# carcomputer_split1_bottom.net
KiCad netlist of a schematic drawn in EAGLE
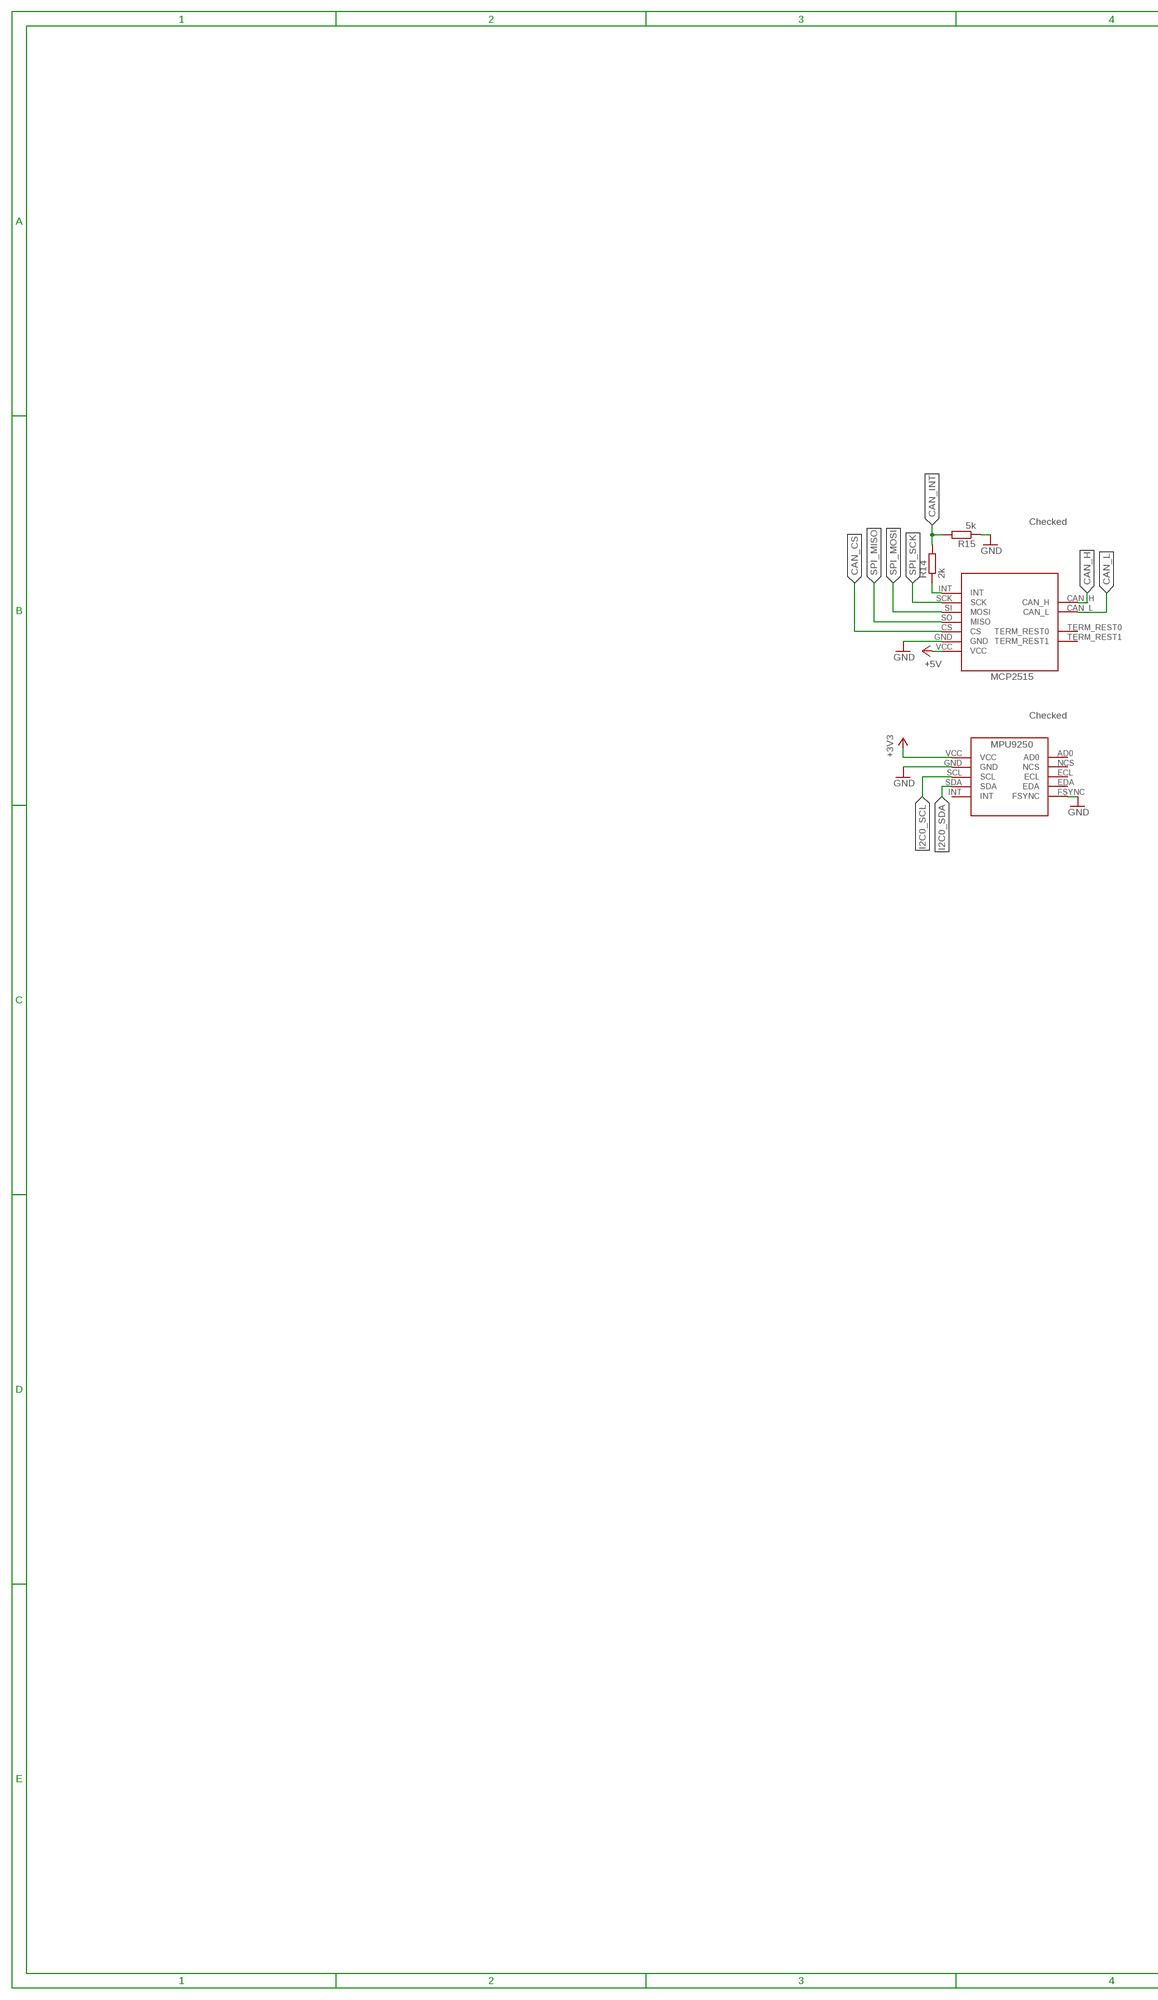
[diagram p0: schematic, sheet 1, part 1 of 2]
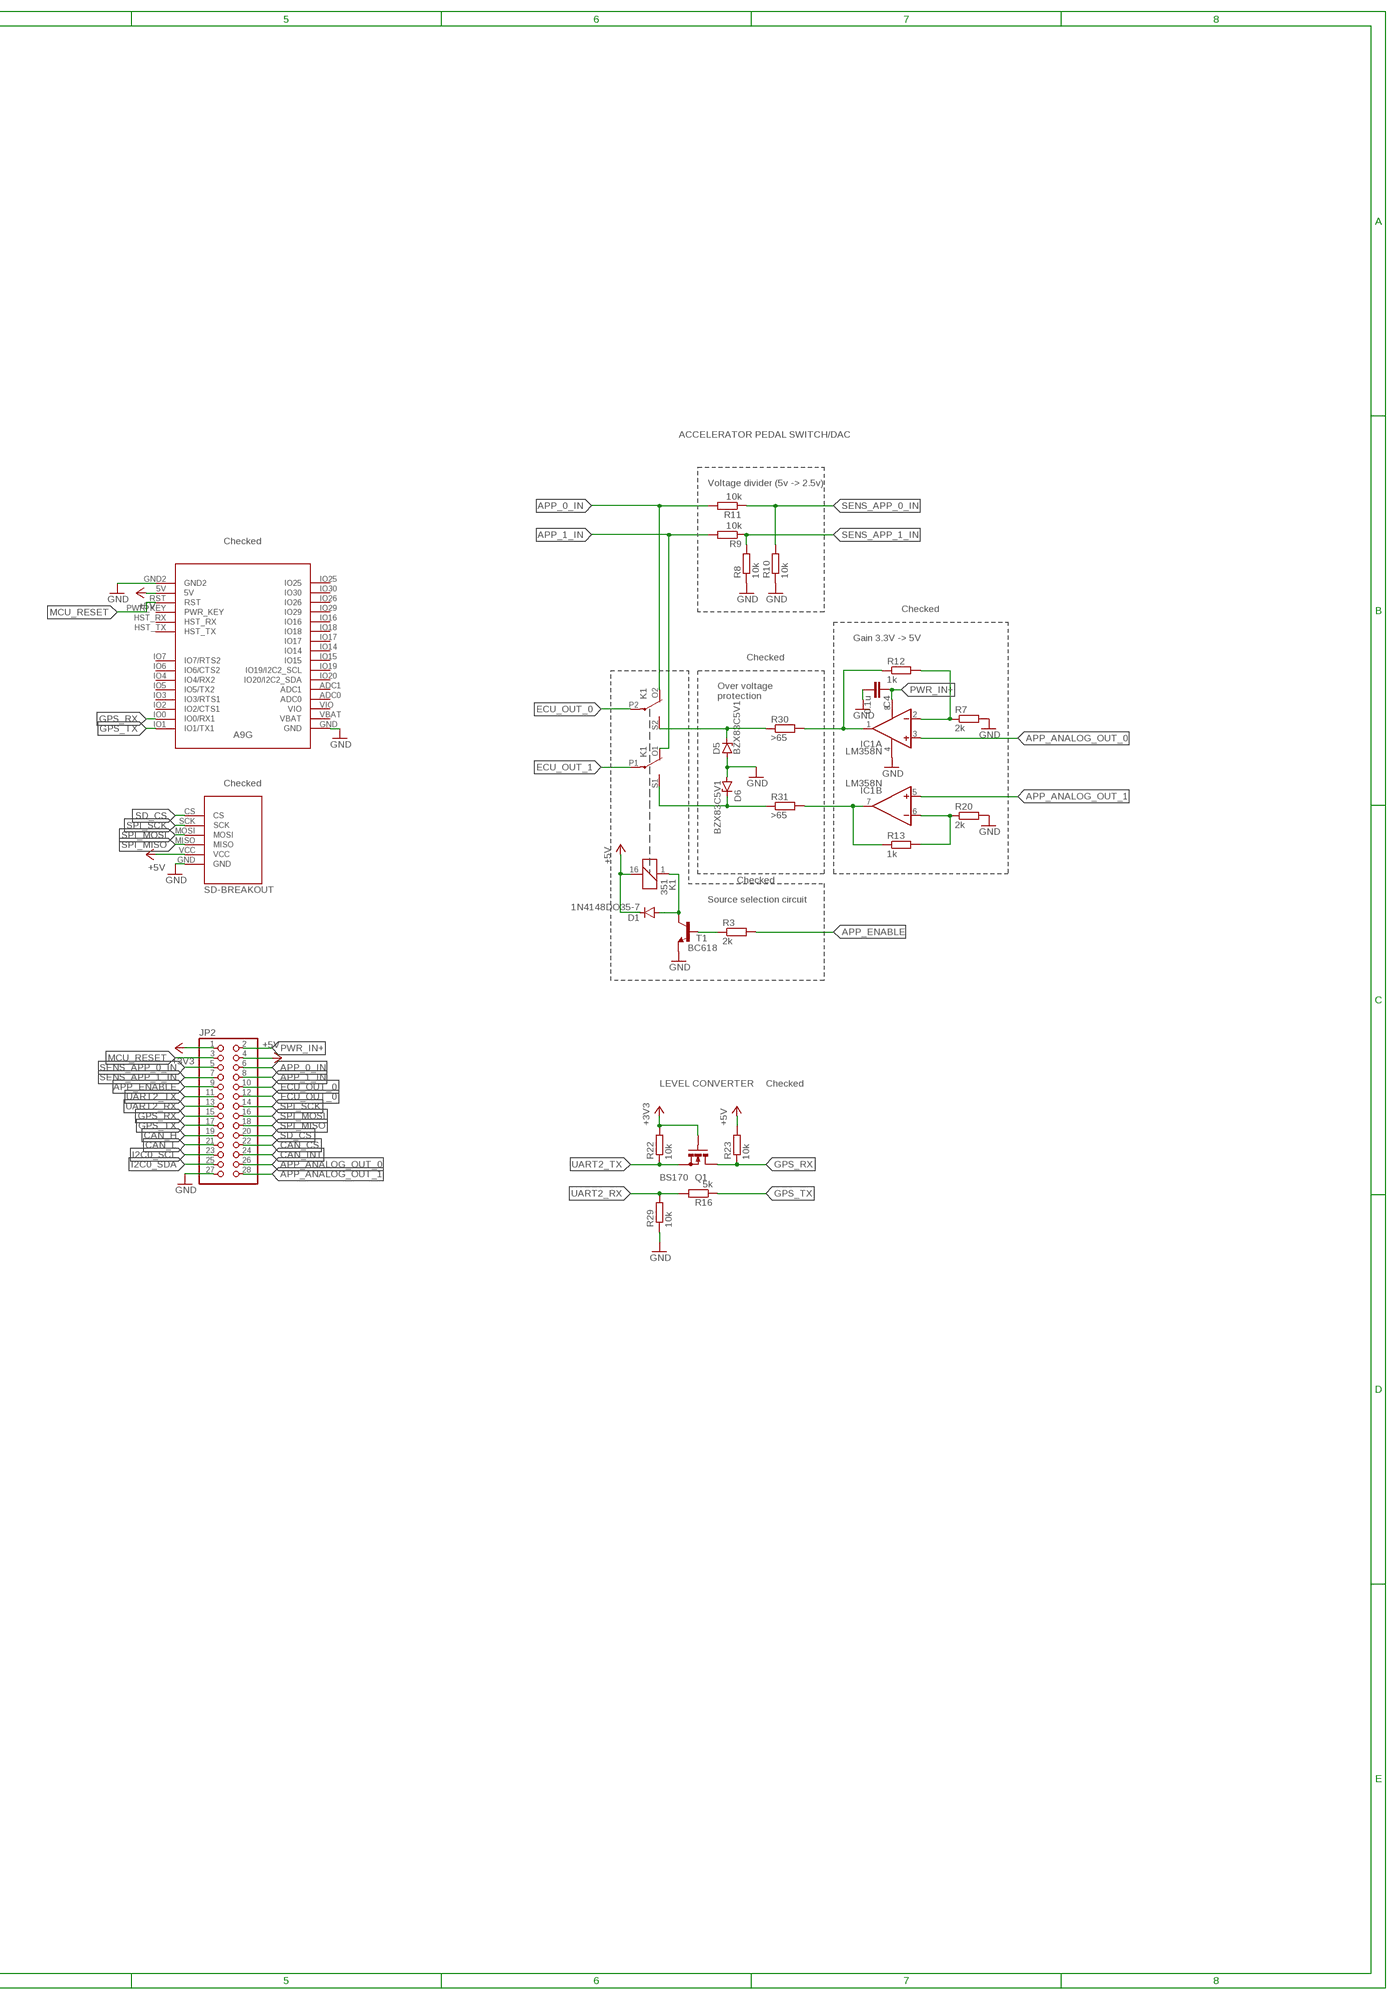
[diagram p1: schematic, sheet 1, part 2 of 2]

(export (version "E")
  (design (tool "Eeschema 10.0.6"))
  (components
    (comp (ref "C4")
      (value "0.1u")
      (footprint "eagle-import:C025-050X050")
      (libsource (lib "eagle-import") (part "C-EU025-050X050"))
    )
    (comp (ref "D1")
      (value "1N4148DO35-7")
      (footprint "eagle-import:DO35-7")
      (libsource (lib "eagle-import") (part "1N4148DO35-7"))
    )
    (comp (ref "D5")
      (value "BZX83C5V1")
      (footprint "eagle-import:DO41Z10")
      (libsource (lib "eagle-import") (part "BZX85"))
    )
    (comp (ref "D6")
      (value "BZX83C5V1")
      (footprint "eagle-import:DO41Z10")
      (libsource (lib "eagle-import") (part "BZX85"))
    )
    (comp (ref "IC1")
      (value "LM358N")
      (footprint "eagle-import:DIL08")
      (libsource (lib "eagle-import") (part "LM358N"))
    )
    (comp (ref "JP2")
      (value "PINHD-2X14")
      (footprint "eagle-import:2X14")
      (libsource (lib "eagle-import") (part "PINHD-2X14"))
    )
    (comp (ref "K1")
      (value "351")
      (footprint "eagle-import:351")
      (libsource (lib "eagle-import") (part "351"))
    )
    (comp (ref "Q1")
      (value "BS170")
      (footprint "eagle-import:SOT54E")
      (libsource (lib "eagle-import") (part "BS170"))
    )
    (comp (ref "R3")
      (value "2k")
      (footprint "eagle-import:0207_7")
      (libsource (lib "eagle-import") (part "R-EU_0207/7"))
    )
    (comp (ref "R7")
      (value "2k")
      (footprint "eagle-import:0207_7")
      (libsource (lib "eagle-import") (part "R-EU_0207/7"))
    )
    (comp (ref "R8")
      (value "10k")
      (footprint "eagle-import:0207_7")
      (libsource (lib "eagle-import") (part "R-EU_0207/7"))
    )
    (comp (ref "R9")
      (value "10k")
      (footprint "eagle-import:0207_7")
      (libsource (lib "eagle-import") (part "R-EU_0207/7"))
    )
    (comp (ref "R10")
      (value "10k")
      (footprint "eagle-import:0207_7")
      (libsource (lib "eagle-import") (part "R-EU_0207/7"))
    )
    (comp (ref "R11")
      (value "10k")
      (footprint "eagle-import:0207_7")
      (libsource (lib "eagle-import") (part "R-EU_0207/7"))
    )
    (comp (ref "R12")
      (value "1k")
      (footprint "eagle-import:0207_7")
      (libsource (lib "eagle-import") (part "R-EU_0207/7"))
    )
    (comp (ref "R13")
      (value "1k")
      (footprint "eagle-import:0207_7")
      (libsource (lib "eagle-import") (part "R-EU_0207/7"))
    )
    (comp (ref "R14")
      (value "2k")
      (footprint "eagle-import:0207_7")
      (libsource (lib "eagle-import") (part "R-EU_0207/7"))
    )
    (comp (ref "R15")
      (value "5k")
      (footprint "eagle-import:0207_7")
      (libsource (lib "eagle-import") (part "R-EU_0207/7"))
    )
    (comp (ref "R16")
      (value "5k")
      (footprint "eagle-import:0207_7")
      (libsource (lib "eagle-import") (part "R-EU_0207/7"))
    )
    (comp (ref "R20")
      (value "2k")
      (footprint "eagle-import:0207_7")
      (libsource (lib "eagle-import") (part "R-EU_0207/7"))
    )
    (comp (ref "R22")
      (value "10k")
      (footprint "eagle-import:0207_7")
      (libsource (lib "eagle-import") (part "R-EU_0207/7"))
    )
    (comp (ref "R23")
      (value "10k")
      (footprint "eagle-import:0207_7")
      (libsource (lib "eagle-import") (part "R-EU_0207/7"))
    )
    (comp (ref "R29")
      (value "10k")
      (footprint "eagle-import:0207_7")
      (libsource (lib "eagle-import") (part "R-EU_0207/7"))
    )
    (comp (ref "R30")
      (value ">65")
      (footprint "eagle-import:0207_7")
      (libsource (lib "eagle-import") (part "R-EU_0207/7"))
    )
    (comp (ref "R31")
      (value ">65")
      (footprint "eagle-import:0207_7")
      (libsource (lib "eagle-import") (part "R-EU_0207/7"))
    )
    (comp (ref "T1")
      (value "BC618")
      (footprint "eagle-import:TO92-EBC")
      (libsource (lib "eagle-import") (part "BC618"))
    )
    (comp (ref "U$2")
      (value "MCP2515_DEVBOARDINVERTED")
      (footprint "eagle-import:MCP2515_DEVBOARD_INVERTED")
      (libsource (lib "eagle-import") (part "MCP2515_DEVBOARDINVERTED"))
    )
    (comp (ref "U$3")
      (value "MPU9250_BREAKOUT")
      (footprint "eagle-import:MPU9250_BREAKOUT")
      (libsource (lib "eagle-import") (part "MPU9250_BREAKOUT"))
    )
    (comp (ref "U$5")
      (value "HKD-MICRO-SD-BREAKOUT")
      (footprint "eagle-import:HKD-MICRO-SD-BREAKOUT")
      (libsource (lib "eagle-import") (part "HKD-MICRO-SD-BREAKOUT"))
    )
    (comp (ref "U$6")
      (value "A9G")
      (footprint "eagle-import:A9G")
      (libsource (lib "eagle-import") (part "A9G"))
    )
  )
  (nets
    (net (code "1") (name "+3V3") (class "Default")
      (node (ref "JP2") (pin "1") (pinfunction "1_1") (pintype "passive"))
      (node (ref "Q1") (pin "G") (pinfunction "G_G") (pintype "passive"))
      (node (ref "R22") (pin "2") (pinfunction "2_2") (pintype "passive"))
      (node (ref "U$3") (pin "VCC") (pinfunction "VCC_VCC") (pintype "bidirectional"))
    )
    (net (code "2") (name "+5V") (class "Default")
      (node (ref "D1") (pin "C") (pinfunction "C_C") (pintype "passive"))
      (node (ref "JP2") (pin "4") (pinfunction "4_4") (pintype "passive"))
      (node (ref "K1") (pin "16") (pinfunction "2_16") (pintype "passive"))
      (node (ref "R23") (pin "2") (pinfunction "2_2") (pintype "passive"))
      (node (ref "U$2") (pin "VCC") (pinfunction "VCC_VCC") (pintype "bidirectional"))
      (node (ref "U$5") (pin "VCC") (pinfunction "VCC_VCC") (pintype "bidirectional"))
      (node (ref "U$6") (pin "5V") (pinfunction "5V_5V") (pintype "bidirectional"))
    )
    (net (code "3") (name "APP_0_IN") (class "Default")
      (node (ref "JP2") (pin "6") (pinfunction "6_6") (pintype "passive"))
      (node (ref "K1") (pin "O2") (pinfunction "O_O2") (pintype "passive"))
      (node (ref "R11") (pin "2") (pinfunction "2_2") (pintype "passive"))
    )
    (net (code "4") (name "APP_1_IN") (class "Default")
      (node (ref "JP2") (pin "8") (pinfunction "8_8") (pintype "passive"))
      (node (ref "K1") (pin "O1") (pinfunction "O_O1") (pintype "passive"))
      (node (ref "R9") (pin "2") (pinfunction "2_2") (pintype "passive"))
    )
    (net (code "5") (name "APP_ANALOG_OUT_0") (class "Default")
      (node (ref "IC1") (pin "3") (pinfunction "+IN_3") (pintype "input"))
      (node (ref "JP2") (pin "26") (pinfunction "26_26") (pintype "passive"))
    )
    (net (code "6") (name "APP_ANALOG_OUT_1") (class "Default")
      (node (ref "IC1") (pin "5") (pinfunction "+IN_5") (pintype "input"))
      (node (ref "JP2") (pin "28") (pinfunction "28_28") (pintype "passive"))
    )
    (net (code "7") (name "APP_ENABLE") (class "Default")
      (node (ref "JP2") (pin "9") (pinfunction "9_9") (pintype "passive"))
      (node (ref "R3") (pin "2") (pinfunction "2_2") (pintype "passive"))
    )
    (net (code "8") (name "CAN_CS") (class "Default")
      (node (ref "JP2") (pin "22") (pinfunction "22_22") (pintype "passive"))
      (node (ref "U$2") (pin "CS") (pinfunction "CS_CS") (pintype "input"))
    )
    (net (code "9") (name "CAN_H") (class "Default")
      (node (ref "JP2") (pin "19") (pinfunction "19_19") (pintype "passive"))
      (node (ref "U$2") (pin "CAN_H") (pinfunction "CAN_H_CAN_H") (pintype "bidirectional"))
    )
    (net (code "10") (name "CAN_INT") (class "Default")
      (node (ref "JP2") (pin "24") (pinfunction "24_24") (pintype "passive"))
      (node (ref "R14") (pin "2") (pinfunction "2_2") (pintype "passive"))
      (node (ref "R15") (pin "2") (pinfunction "2_2") (pintype "passive"))
    )
    (net (code "11") (name "CAN_L") (class "Default")
      (node (ref "JP2") (pin "21") (pinfunction "21_21") (pintype "passive"))
      (node (ref "U$2") (pin "CAN_L") (pinfunction "CAN_L_CAN_L") (pintype "bidirectional"))
    )
    (net (code "12") (name "ECU_OUT_0") (class "Default")
      (node (ref "JP2") (pin "10") (pinfunction "10_10") (pintype "passive"))
      (node (ref "JP2") (pin "12") (pinfunction "12_12") (pintype "passive"))
      (node (ref "K1") (pin "P2") (pinfunction "P_P2") (pintype "passive"))
    )
    (net (code "13") (name "ECU_OUT_1") (class "Default")
      (node (ref "K1") (pin "P1") (pinfunction "P_P1") (pintype "passive"))
    )
    (net (code "14") (name "GND") (class "Default")
      (node (ref "C4") (pin "2") (pinfunction "2_2") (pintype "passive"))
      (node (ref "D5") (pin "A") (pinfunction "A_A") (pintype "passive"))
      (node (ref "D6") (pin "A") (pinfunction "A_A") (pintype "passive"))
      (node (ref "IC1") (pin "4") (pinfunction "V-_4") (pintype "power_in"))
      (node (ref "JP2") (pin "27") (pinfunction "27_27") (pintype "passive"))
      (node (ref "R10") (pin "1") (pinfunction "1_1") (pintype "passive"))
      (node (ref "R15") (pin "1") (pinfunction "1_1") (pintype "passive"))
      (node (ref "R20") (pin "2") (pinfunction "2_2") (pintype "passive"))
      (node (ref "R29") (pin "1") (pinfunction "1_1") (pintype "passive"))
      (node (ref "R7") (pin "2") (pinfunction "2_2") (pintype "passive"))
      (node (ref "R8") (pin "1") (pinfunction "1_1") (pintype "passive"))
      (node (ref "T1") (pin "E") (pinfunction "E_E") (pintype "passive"))
      (node (ref "U$2") (pin "GND") (pinfunction "GND_GND") (pintype "bidirectional"))
      (node (ref "U$3") (pin "FSYNC") (pinfunction "FSYNC_FSYNC") (pintype "bidirectional"))
      (node (ref "U$3") (pin "GND") (pinfunction "GND_GND") (pintype "bidirectional"))
      (node (ref "U$5") (pin "GND") (pinfunction "GND_GND") (pintype "bidirectional"))
      (node (ref "U$6") (pin "GND") (pinfunction "GND_GND") (pintype "bidirectional"))
      (node (ref "U$6") (pin "GND2") (pinfunction "GND2_GND2") (pintype "bidirectional"))
    )
    (net (code "15") (name "GPS_RX") (class "Default")
      (node (ref "JP2") (pin "15") (pinfunction "15_15") (pintype "passive"))
      (node (ref "Q1") (pin "D") (pinfunction "D_D") (pintype "passive"))
      (node (ref "R23") (pin "1") (pinfunction "1_1") (pintype "passive"))
      (node (ref "U$6") (pin "IO0") (pinfunction "IO0/RX1_IO0") (pintype "bidirectional"))
    )
    (net (code "16") (name "GPS_TX") (class "Default")
      (node (ref "JP2") (pin "17") (pinfunction "17_17") (pintype "passive"))
      (node (ref "R16") (pin "1") (pinfunction "1_1") (pintype "passive"))
      (node (ref "U$6") (pin "IO1") (pinfunction "IO1/TX1_IO1") (pintype "bidirectional"))
    )
    (net (code "17") (name "I2C0_SCL") (class "Default")
      (node (ref "JP2") (pin "23") (pinfunction "23_23") (pintype "passive"))
      (node (ref "U$3") (pin "SCL") (pinfunction "SCL_SCL") (pintype "bidirectional"))
    )
    (net (code "18") (name "I2C0_SDA") (class "Default")
      (node (ref "JP2") (pin "25") (pinfunction "25_25") (pintype "passive"))
      (node (ref "U$3") (pin "SDA") (pinfunction "SDA_SDA") (pintype "bidirectional"))
    )
    (net (code "19") (name "MCU_RESET") (class "Default")
      (node (ref "JP2") (pin "3") (pinfunction "3_3") (pintype "passive"))
      (node (ref "U$6") (pin "RST") (pinfunction "RST_RST") (pintype "bidirectional"))
    )
    (net (code "20") (name "Net-(D1-PadA)") (class "Default")
      (node (ref "D1") (pin "A") (pinfunction "A_A") (pintype "passive"))
      (node (ref "K1") (pin "1") (pinfunction "1_1") (pintype "passive"))
      (node (ref "T1") (pin "C") (pinfunction "C_C") (pintype "passive"))
    )
    (net (code "21") (name "Net-(IC1A--IN)") (class "Default")
      (node (ref "IC1") (pin "2") (pinfunction "-IN_2") (pintype "input"))
      (node (ref "R12") (pin "2") (pinfunction "2_2") (pintype "passive"))
      (node (ref "R7") (pin "1") (pinfunction "1_1") (pintype "passive"))
    )
    (net (code "22") (name "Net-(IC1A-OUT)") (class "Default")
      (node (ref "IC1") (pin "1") (pinfunction "OUT_1") (pintype "output"))
      (node (ref "R12") (pin "1") (pinfunction "1_1") (pintype "passive"))
      (node (ref "R30") (pin "2") (pinfunction "2_2") (pintype "passive"))
    )
    (net (code "23") (name "Net-(IC1B--IN)") (class "Default")
      (node (ref "IC1") (pin "6") (pinfunction "-IN_6") (pintype "input"))
      (node (ref "R13") (pin "2") (pinfunction "2_2") (pintype "passive"))
      (node (ref "R20") (pin "1") (pinfunction "1_1") (pintype "passive"))
    )
    (net (code "24") (name "Net-(IC1B-OUT)") (class "Default")
      (node (ref "IC1") (pin "7") (pinfunction "OUT_7") (pintype "output"))
      (node (ref "R13") (pin "1") (pinfunction "1_1") (pintype "passive"))
      (node (ref "R31") (pin "2") (pinfunction "2_2") (pintype "passive"))
    )
    (net (code "25") (name "Net-(K1B-S)") (class "Default")
      (node (ref "D6") (pin "C") (pinfunction "C_C") (pintype "passive"))
      (node (ref "K1") (pin "S1") (pinfunction "S_S1") (pintype "passive"))
      (node (ref "R31") (pin "1") (pinfunction "1_1") (pintype "passive"))
    )
    (net (code "26") (name "Net-(K1C-S)") (class "Default")
      (node (ref "D5") (pin "C") (pinfunction "C_C") (pintype "passive"))
      (node (ref "K1") (pin "S2") (pinfunction "S_S2") (pintype "passive"))
      (node (ref "R30") (pin "1") (pinfunction "1_1") (pintype "passive"))
    )
    (net (code "27") (name "Net-(R3-Pad1)") (class "Default")
      (node (ref "R3") (pin "1") (pinfunction "1_1") (pintype "passive"))
      (node (ref "T1") (pin "B") (pinfunction "B_B") (pintype "passive"))
    )
    (net (code "28") (name "Net-(R14-Pad1)") (class "Default")
      (node (ref "R14") (pin "1") (pinfunction "1_1") (pintype "passive"))
      (node (ref "U$2") (pin "INT") (pinfunction "INT_INT") (pintype "output"))
    )
    (net (code "29") (name "PWR_IN+") (class "Default")
      (node (ref "C4") (pin "1") (pinfunction "1_1") (pintype "passive"))
      (node (ref "IC1") (pin "8") (pinfunction "V+_8") (pintype "power_in"))
      (node (ref "JP2") (pin "2") (pinfunction "2_2") (pintype "passive"))
    )
    (net (code "30") (name "SD_CS") (class "Default")
      (node (ref "JP2") (pin "20") (pinfunction "20_20") (pintype "passive"))
      (node (ref "U$5") (pin "CS") (pinfunction "CS_CS") (pintype "bidirectional"))
    )
    (net (code "31") (name "SENS_APP_0_IN") (class "Default")
      (node (ref "JP2") (pin "5") (pinfunction "5_5") (pintype "passive"))
      (node (ref "R10") (pin "2") (pinfunction "2_2") (pintype "passive"))
      (node (ref "R11") (pin "1") (pinfunction "1_1") (pintype "passive"))
    )
    (net (code "32") (name "SENS_APP_1_IN") (class "Default")
      (node (ref "JP2") (pin "7") (pinfunction "7_7") (pintype "passive"))
      (node (ref "R8") (pin "2") (pinfunction "2_2") (pintype "passive"))
      (node (ref "R9") (pin "1") (pinfunction "1_1") (pintype "passive"))
    )
    (net (code "33") (name "SPI_MISO") (class "Default")
      (node (ref "JP2") (pin "18") (pinfunction "18_18") (pintype "passive"))
      (node (ref "U$2") (pin "SO") (pinfunction "MISO_SO") (pintype "output"))
      (node (ref "U$5") (pin "MISO") (pinfunction "MISO_MISO") (pintype "bidirectional"))
    )
    (net (code "34") (name "SPI_MOSI") (class "Default")
      (node (ref "JP2") (pin "16") (pinfunction "16_16") (pintype "passive"))
      (node (ref "U$2") (pin "SI") (pinfunction "MOSI_SI") (pintype "input"))
      (node (ref "U$5") (pin "MOSI") (pinfunction "MOSI_MOSI") (pintype "bidirectional"))
    )
    (net (code "35") (name "SPI_SCK") (class "Default")
      (node (ref "JP2") (pin "14") (pinfunction "14_14") (pintype "passive"))
      (node (ref "U$2") (pin "SCK") (pinfunction "SCK_SCK") (pintype "input"))
      (node (ref "U$5") (pin "SCK") (pinfunction "SCK_SCK") (pintype "bidirectional"))
    )
    (net (code "36") (name "UART2_RX") (class "Default")
      (node (ref "JP2") (pin "13") (pinfunction "13_13") (pintype "passive"))
      (node (ref "R16") (pin "2") (pinfunction "2_2") (pintype "passive"))
      (node (ref "R29") (pin "2") (pinfunction "2_2") (pintype "passive"))
    )
    (net (code "37") (name "UART2_TX") (class "Default")
      (node (ref "JP2") (pin "11") (pinfunction "11_11") (pintype "passive"))
      (node (ref "Q1") (pin "S") (pinfunction "S_S") (pintype "passive"))
      (node (ref "R22") (pin "1") (pinfunction "1_1") (pintype "passive"))
    )
    (net (code "38") (name "unconnected-(U$2-PadTERM_REST0)") (class "Default")
      (node (ref "U$2") (pin "TERM_REST0") (pinfunction "TERM_REST0_TERM_REST0") (pintype "bidirectional"))
    )
    (net (code "39") (name "unconnected-(U$2-PadTERM_REST1)") (class "Default")
      (node (ref "U$2") (pin "TERM_REST1") (pinfunction "TERM_REST1_TERM_REST1") (pintype "bidirectional"))
    )
    (net (code "40") (name "unconnected-(U$3-PadAD0)") (class "Default")
      (node (ref "U$3") (pin "AD0") (pinfunction "AD0_AD0") (pintype "bidirectional"))
    )
    (net (code "41") (name "unconnected-(U$3-PadECL)") (class "Default")
      (node (ref "U$3") (pin "ECL") (pinfunction "ECL_ECL") (pintype "bidirectional"))
    )
    (net (code "42") (name "unconnected-(U$3-PadEDA)") (class "Default")
      (node (ref "U$3") (pin "EDA") (pinfunction "EDA_EDA") (pintype "bidirectional"))
    )
    (net (code "43") (name "unconnected-(U$3-PadINT)") (class "Default")
      (node (ref "U$3") (pin "INT") (pinfunction "INT_INT") (pintype "bidirectional"))
    )
    (net (code "44") (name "unconnected-(U$3-PadNCS)") (class "Default")
      (node (ref "U$3") (pin "NCS") (pinfunction "NCS_NCS") (pintype "bidirectional"))
    )
    (net (code "45") (name "unconnected-(U$6-IO2{slash}CTS1-PadIO2)") (class "Default")
      (node (ref "U$6") (pin "IO2") (pinfunction "IO2/CTS1_IO2") (pintype "bidirectional"))
    )
    (net (code "46") (name "unconnected-(U$6-IO3{slash}RTS1-PadIO3)") (class "Default")
      (node (ref "U$6") (pin "IO3") (pinfunction "IO3/RTS1_IO3") (pintype "bidirectional"))
    )
    (net (code "47") (name "unconnected-(U$6-IO4{slash}RX2-PadIO4)") (class "Default")
      (node (ref "U$6") (pin "IO4") (pinfunction "IO4/RX2_IO4") (pintype "bidirectional"))
    )
    (net (code "48") (name "unconnected-(U$6-IO5{slash}TX2-PadIO5)") (class "Default")
      (node (ref "U$6") (pin "IO5") (pinfunction "IO5/TX2_IO5") (pintype "bidirectional"))
    )
    (net (code "49") (name "unconnected-(U$6-IO6{slash}CTS2-PadIO6)") (class "Default")
      (node (ref "U$6") (pin "IO6") (pinfunction "IO6/CTS2_IO6") (pintype "bidirectional"))
    )
    (net (code "50") (name "unconnected-(U$6-IO7{slash}RTS2-PadIO7)") (class "Default")
      (node (ref "U$6") (pin "IO7") (pinfunction "IO7/RTS2_IO7") (pintype "bidirectional"))
    )
    (net (code "51") (name "unconnected-(U$6-IO19{slash}I2C2_SCL-PadIO19)") (class "Default")
      (node (ref "U$6") (pin "IO19") (pinfunction "IO19/I2C2_SCL_IO19") (pintype "bidirectional"))
    )
    (net (code "52") (name "unconnected-(U$6-IO20{slash}I2C2_SDA-PadIO20)") (class "Default")
      (node (ref "U$6") (pin "IO20") (pinfunction "IO20/I2C2_SDA_IO20") (pintype "bidirectional"))
    )
    (net (code "53") (name "unconnected-(U$6-PadADC0)") (class "Default")
      (node (ref "U$6") (pin "ADC0") (pinfunction "ADC0_ADC0") (pintype "bidirectional"))
    )
    (net (code "54") (name "unconnected-(U$6-PadADC1)") (class "Default")
      (node (ref "U$6") (pin "ADC1") (pinfunction "ADC1_ADC1") (pintype "bidirectional"))
    )
    (net (code "55") (name "unconnected-(U$6-PadHST_RX)") (class "Default")
      (node (ref "U$6") (pin "HST_RX") (pinfunction "HST_RX_HST_RX") (pintype "bidirectional"))
    )
    (net (code "56") (name "unconnected-(U$6-PadHST_TX)") (class "Default")
      (node (ref "U$6") (pin "HST_TX") (pinfunction "HST_TX_HST_TX") (pintype "bidirectional"))
    )
    (net (code "57") (name "unconnected-(U$6-PadIO14)") (class "Default")
      (node (ref "U$6") (pin "IO14") (pinfunction "IO14_IO14") (pintype "bidirectional"))
    )
    (net (code "58") (name "unconnected-(U$6-PadIO15)") (class "Default")
      (node (ref "U$6") (pin "IO15") (pinfunction "IO15_IO15") (pintype "bidirectional"))
    )
    (net (code "59") (name "unconnected-(U$6-PadIO16)") (class "Default")
      (node (ref "U$6") (pin "IO16") (pinfunction "IO16_IO16") (pintype "bidirectional"))
    )
    (net (code "60") (name "unconnected-(U$6-PadIO17)") (class "Default")
      (node (ref "U$6") (pin "IO17") (pinfunction "IO17_IO17") (pintype "bidirectional"))
    )
    (net (code "61") (name "unconnected-(U$6-PadIO18)") (class "Default")
      (node (ref "U$6") (pin "IO18") (pinfunction "IO18_IO18") (pintype "bidirectional"))
    )
    (net (code "62") (name "unconnected-(U$6-PadIO25)") (class "Default")
      (node (ref "U$6") (pin "IO25") (pinfunction "IO25_IO25") (pintype "bidirectional"))
    )
    (net (code "63") (name "unconnected-(U$6-PadIO26)") (class "Default")
      (node (ref "U$6") (pin "IO26") (pinfunction "IO26_IO26") (pintype "bidirectional"))
    )
    (net (code "64") (name "unconnected-(U$6-PadIO29)") (class "Default")
      (node (ref "U$6") (pin "IO29") (pinfunction "IO29_IO29") (pintype "bidirectional"))
    )
    (net (code "65") (name "unconnected-(U$6-PadIO30)") (class "Default")
      (node (ref "U$6") (pin "IO30") (pinfunction "IO30_IO30") (pintype "bidirectional"))
    )
    (net (code "66") (name "unconnected-(U$6-PadPWR_KEY)") (class "Default")
      (node (ref "U$6") (pin "PWR_KEY") (pinfunction "PWR_KEY_PWR_KEY") (pintype "bidirectional"))
    )
    (net (code "67") (name "unconnected-(U$6-PadVBAT)") (class "Default")
      (node (ref "U$6") (pin "VBAT") (pinfunction "VBAT_VBAT") (pintype "bidirectional"))
    )
    (net (code "68") (name "unconnected-(U$6-PadVIO)") (class "Default")
      (node (ref "U$6") (pin "VIO") (pinfunction "VIO_VIO") (pintype "bidirectional"))
    )
  )
)
